# Bus-Pirate-v3-Breakout.net
KiCad netlist of a schematic drawn in EAGLE
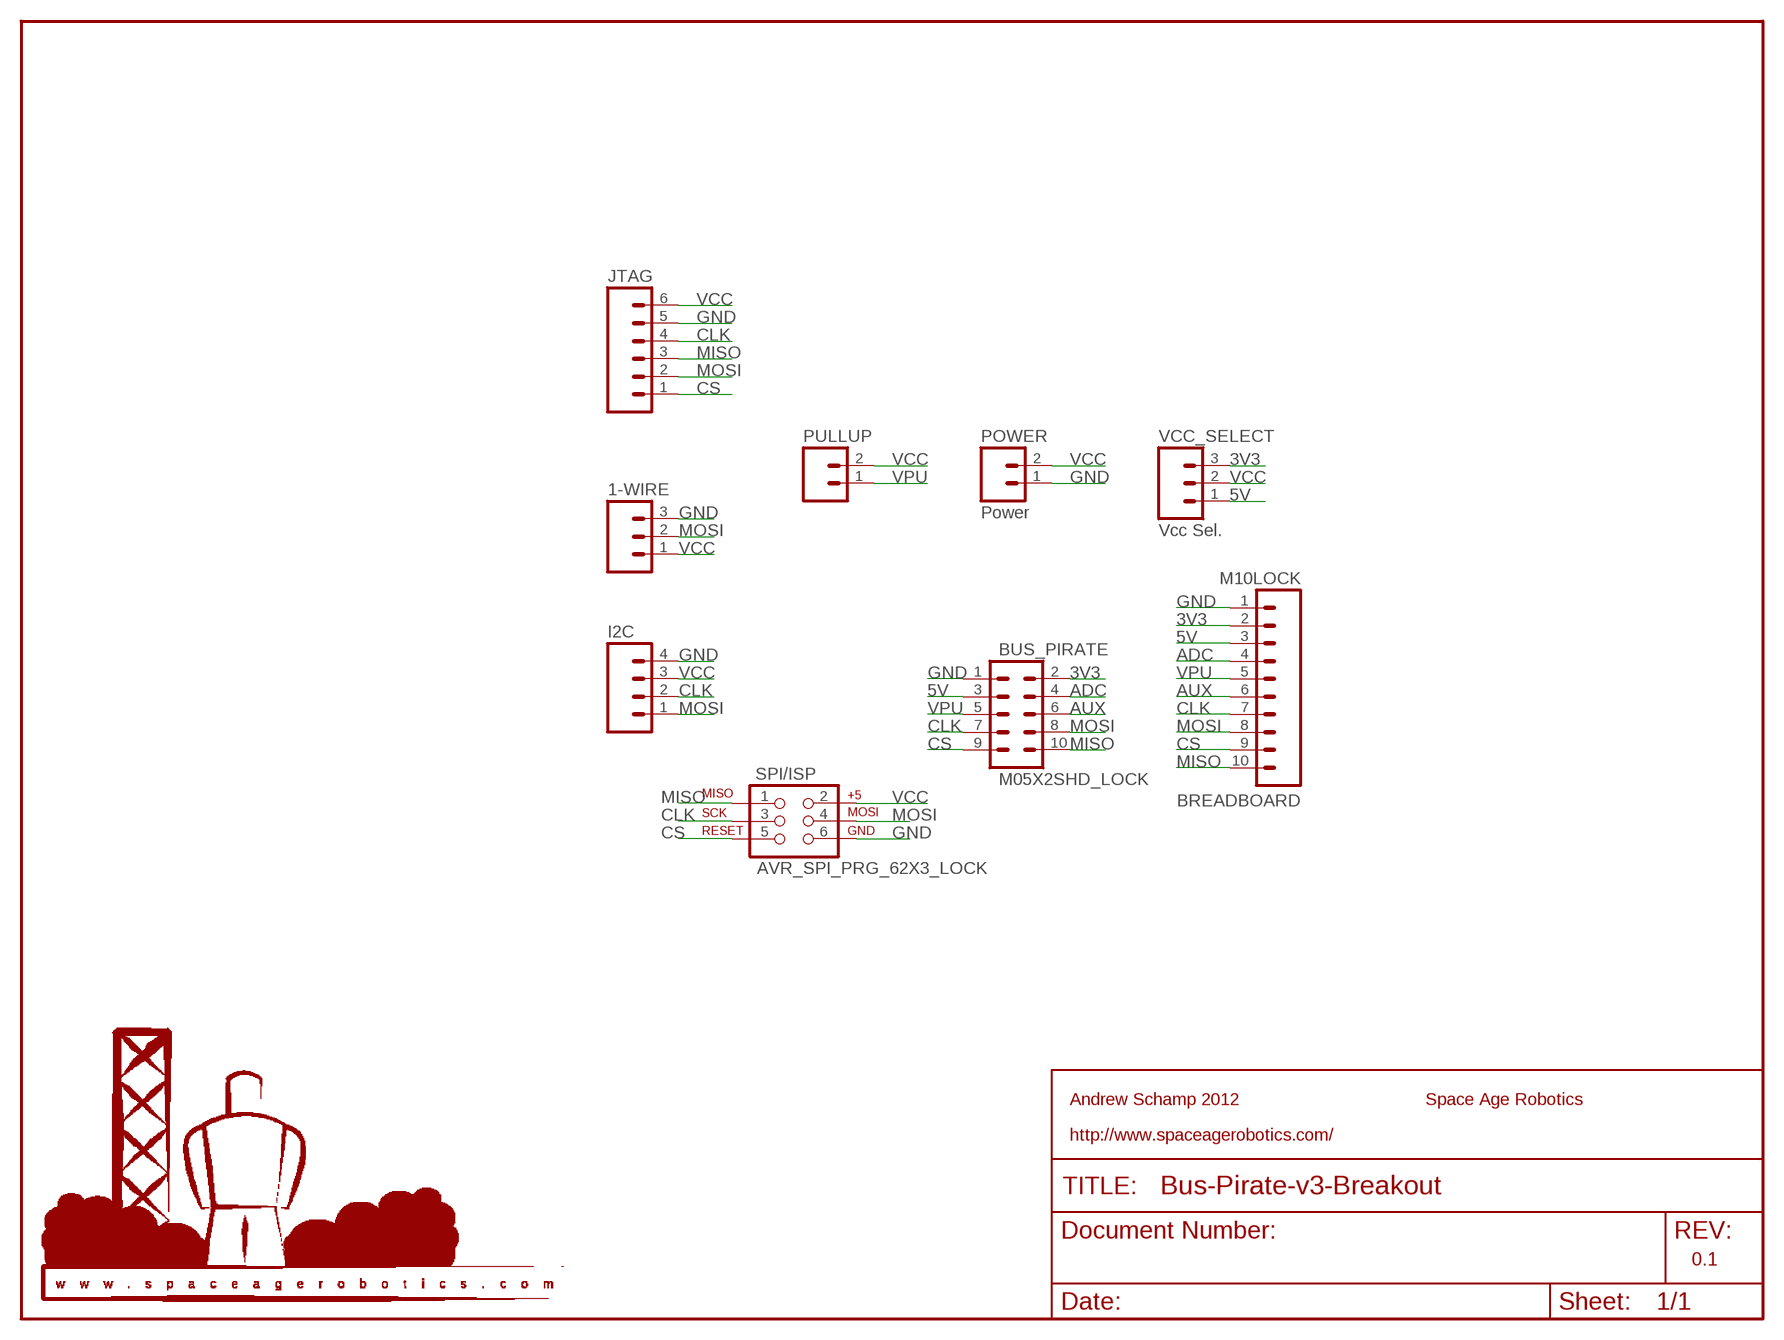
[diagram p0: schematic, sheet 1]

(export (version "E")
  (design (tool "Eeschema 10.0.6"))
  (components
    (comp (ref "1-WIRE")
      (value "M03LOCK")
      (footprint "eagle-import:1X03_LOCK")
      (libsource (lib "eagle-import") (part "M03LOCK"))
    )
    (comp (ref "BREADBOARD")
      (value "M10LOCK")
      (footprint "eagle-import:1X10_LOCK")
      (libsource (lib "eagle-import") (part "M10LOCK"))
    )
    (comp (ref "BUS_PIRATE")
      (value "M05X2SHD_LOCK")
      (footprint "eagle-import:2X5-LOCK")
      (libsource (lib "eagle-import") (part "M05X2SHD_LOCK"))
    )
    (comp (ref "I2C")
      (value "M04LOCK")
      (footprint "eagle-import:1X04_LOCK")
      (libsource (lib "eagle-import") (part "M04LOCK"))
    )
    (comp (ref "JTAG")
      (value "M06LOCK")
      (footprint "eagle-import:1X06_LOCK")
      (libsource (lib "eagle-import") (part "M06LOCK"))
    )
    (comp (ref "POWER")
      (value "Power")
      (footprint "eagle-import:1X02_LOCK")
      (libsource (lib "eagle-import") (part "M02LOCK"))
    )
    (comp (ref "PULLUP")
      (value "M02LOCK")
      (footprint "eagle-import:1X02_LOCK")
      (libsource (lib "eagle-import") (part "M02LOCK"))
    )
    (comp (ref "SPI/ISP")
      (value "AVR_SPI_PRG_62X3_LOCK")
      (footprint "eagle-import:2X3_LOCK")
      (libsource (lib "eagle-import") (part "AVR_SPI_PRG_62X3_LOCK"))
    )
    (comp (ref "U$2")
      (value "LOGO_SPACE_AGE_ROBOTICS0.48*0.27")
      (footprint "eagle-import:LOGO_SPACE_AGE_ROBOTICS_SMALL_0.48X0.27")
      (libsource (lib "eagle-import") (part "LOGO_SPACE_AGE_ROBOTICS0.480.27"))
    )
    (comp (ref "VCC_SELECT")
      (value "Vcc Sel.")
      (footprint "eagle-import:1X03_LOCK")
      (libsource (lib "eagle-import") (part "M03LOCK"))
    )
  )
  (nets
    (net (code "1") (name "/3V3") (class "Default")
      (node (ref "BREADBOARD") (pin "2") (pinfunction "2_2") (pintype "passive"))
      (node (ref "BUS_PIRATE") (pin "2") (pinfunction "2_2") (pintype "passive"))
      (node (ref "VCC_SELECT") (pin "3") (pinfunction "3_3") (pintype "passive"))
    )
    (net (code "2") (name "/5V") (class "Default")
      (node (ref "BREADBOARD") (pin "3") (pinfunction "3_3") (pintype "passive"))
      (node (ref "BUS_PIRATE") (pin "3") (pinfunction "3_3") (pintype "passive"))
      (node (ref "VCC_SELECT") (pin "1") (pinfunction "1_1") (pintype "passive"))
    )
    (net (code "3") (name "/ADC") (class "Default")
      (node (ref "BREADBOARD") (pin "4") (pinfunction "4_4") (pintype "passive"))
      (node (ref "BUS_PIRATE") (pin "4") (pinfunction "4_4") (pintype "passive"))
    )
    (net (code "4") (name "/AUX") (class "Default")
      (node (ref "BREADBOARD") (pin "6") (pinfunction "6_6") (pintype "passive"))
      (node (ref "BUS_PIRATE") (pin "6") (pinfunction "6_6") (pintype "passive"))
    )
    (net (code "5") (name "/CLK") (class "Default")
      (node (ref "BREADBOARD") (pin "7") (pinfunction "7_7") (pintype "passive"))
      (node (ref "BUS_PIRATE") (pin "7") (pinfunction "7_7") (pintype "passive"))
      (node (ref "I2C") (pin "2") (pinfunction "2_2") (pintype "passive"))
      (node (ref "JTAG") (pin "4") (pinfunction "4_4") (pintype "passive"))
      (node (ref "SPI/ISP") (pin "3") (pinfunction "3_3") (pintype "passive"))
    )
    (net (code "6") (name "/CS") (class "Default")
      (node (ref "BREADBOARD") (pin "9") (pinfunction "9_9") (pintype "passive"))
      (node (ref "BUS_PIRATE") (pin "9") (pinfunction "9_9") (pintype "passive"))
      (node (ref "JTAG") (pin "1") (pinfunction "1_1") (pintype "passive"))
      (node (ref "SPI/ISP") (pin "5") (pinfunction "5_5") (pintype "passive"))
    )
    (net (code "7") (name "/GND") (class "Default")
      (node (ref "1-WIRE") (pin "3") (pinfunction "3_3") (pintype "passive"))
      (node (ref "BREADBOARD") (pin "1") (pinfunction "1_1") (pintype "passive"))
      (node (ref "BUS_PIRATE") (pin "1") (pinfunction "1_1") (pintype "passive"))
      (node (ref "I2C") (pin "4") (pinfunction "4_4") (pintype "passive"))
      (node (ref "JTAG") (pin "5") (pinfunction "5_5") (pintype "passive"))
      (node (ref "POWER") (pin "1") (pinfunction "1_1") (pintype "passive"))
      (node (ref "SPI/ISP") (pin "6") (pinfunction "6_6") (pintype "passive"))
    )
    (net (code "8") (name "/MISO") (class "Default")
      (node (ref "BREADBOARD") (pin "10") (pinfunction "10_10") (pintype "passive"))
      (node (ref "BUS_PIRATE") (pin "10") (pinfunction "10_10") (pintype "passive"))
      (node (ref "JTAG") (pin "3") (pinfunction "3_3") (pintype "passive"))
      (node (ref "SPI/ISP") (pin "1") (pinfunction "1_1") (pintype "passive"))
    )
    (net (code "9") (name "/MOSI") (class "Default")
      (node (ref "1-WIRE") (pin "2") (pinfunction "2_2") (pintype "passive"))
      (node (ref "BREADBOARD") (pin "8") (pinfunction "8_8") (pintype "passive"))
      (node (ref "BUS_PIRATE") (pin "8") (pinfunction "8_8") (pintype "passive"))
      (node (ref "I2C") (pin "1") (pinfunction "1_1") (pintype "passive"))
      (node (ref "JTAG") (pin "2") (pinfunction "2_2") (pintype "passive"))
      (node (ref "SPI/ISP") (pin "4") (pinfunction "4_4") (pintype "passive"))
    )
    (net (code "10") (name "/VCC") (class "Default")
      (node (ref "1-WIRE") (pin "1") (pinfunction "1_1") (pintype "passive"))
      (node (ref "I2C") (pin "3") (pinfunction "3_3") (pintype "passive"))
      (node (ref "JTAG") (pin "6") (pinfunction "6_6") (pintype "passive"))
      (node (ref "POWER") (pin "2") (pinfunction "2_2") (pintype "passive"))
      (node (ref "PULLUP") (pin "2") (pinfunction "2_2") (pintype "passive"))
      (node (ref "SPI/ISP") (pin "2") (pinfunction "2_2") (pintype "passive"))
      (node (ref "VCC_SELECT") (pin "2") (pinfunction "2_2") (pintype "passive"))
    )
    (net (code "11") (name "/VPU") (class "Default")
      (node (ref "BREADBOARD") (pin "5") (pinfunction "5_5") (pintype "passive"))
      (node (ref "BUS_PIRATE") (pin "5") (pinfunction "5_5") (pintype "passive"))
      (node (ref "PULLUP") (pin "1") (pinfunction "1_1") (pintype "passive"))
    )
  )
)
